# stm32-board-adapter.net
KiCad netlist of a schematic drawn in EAGLE
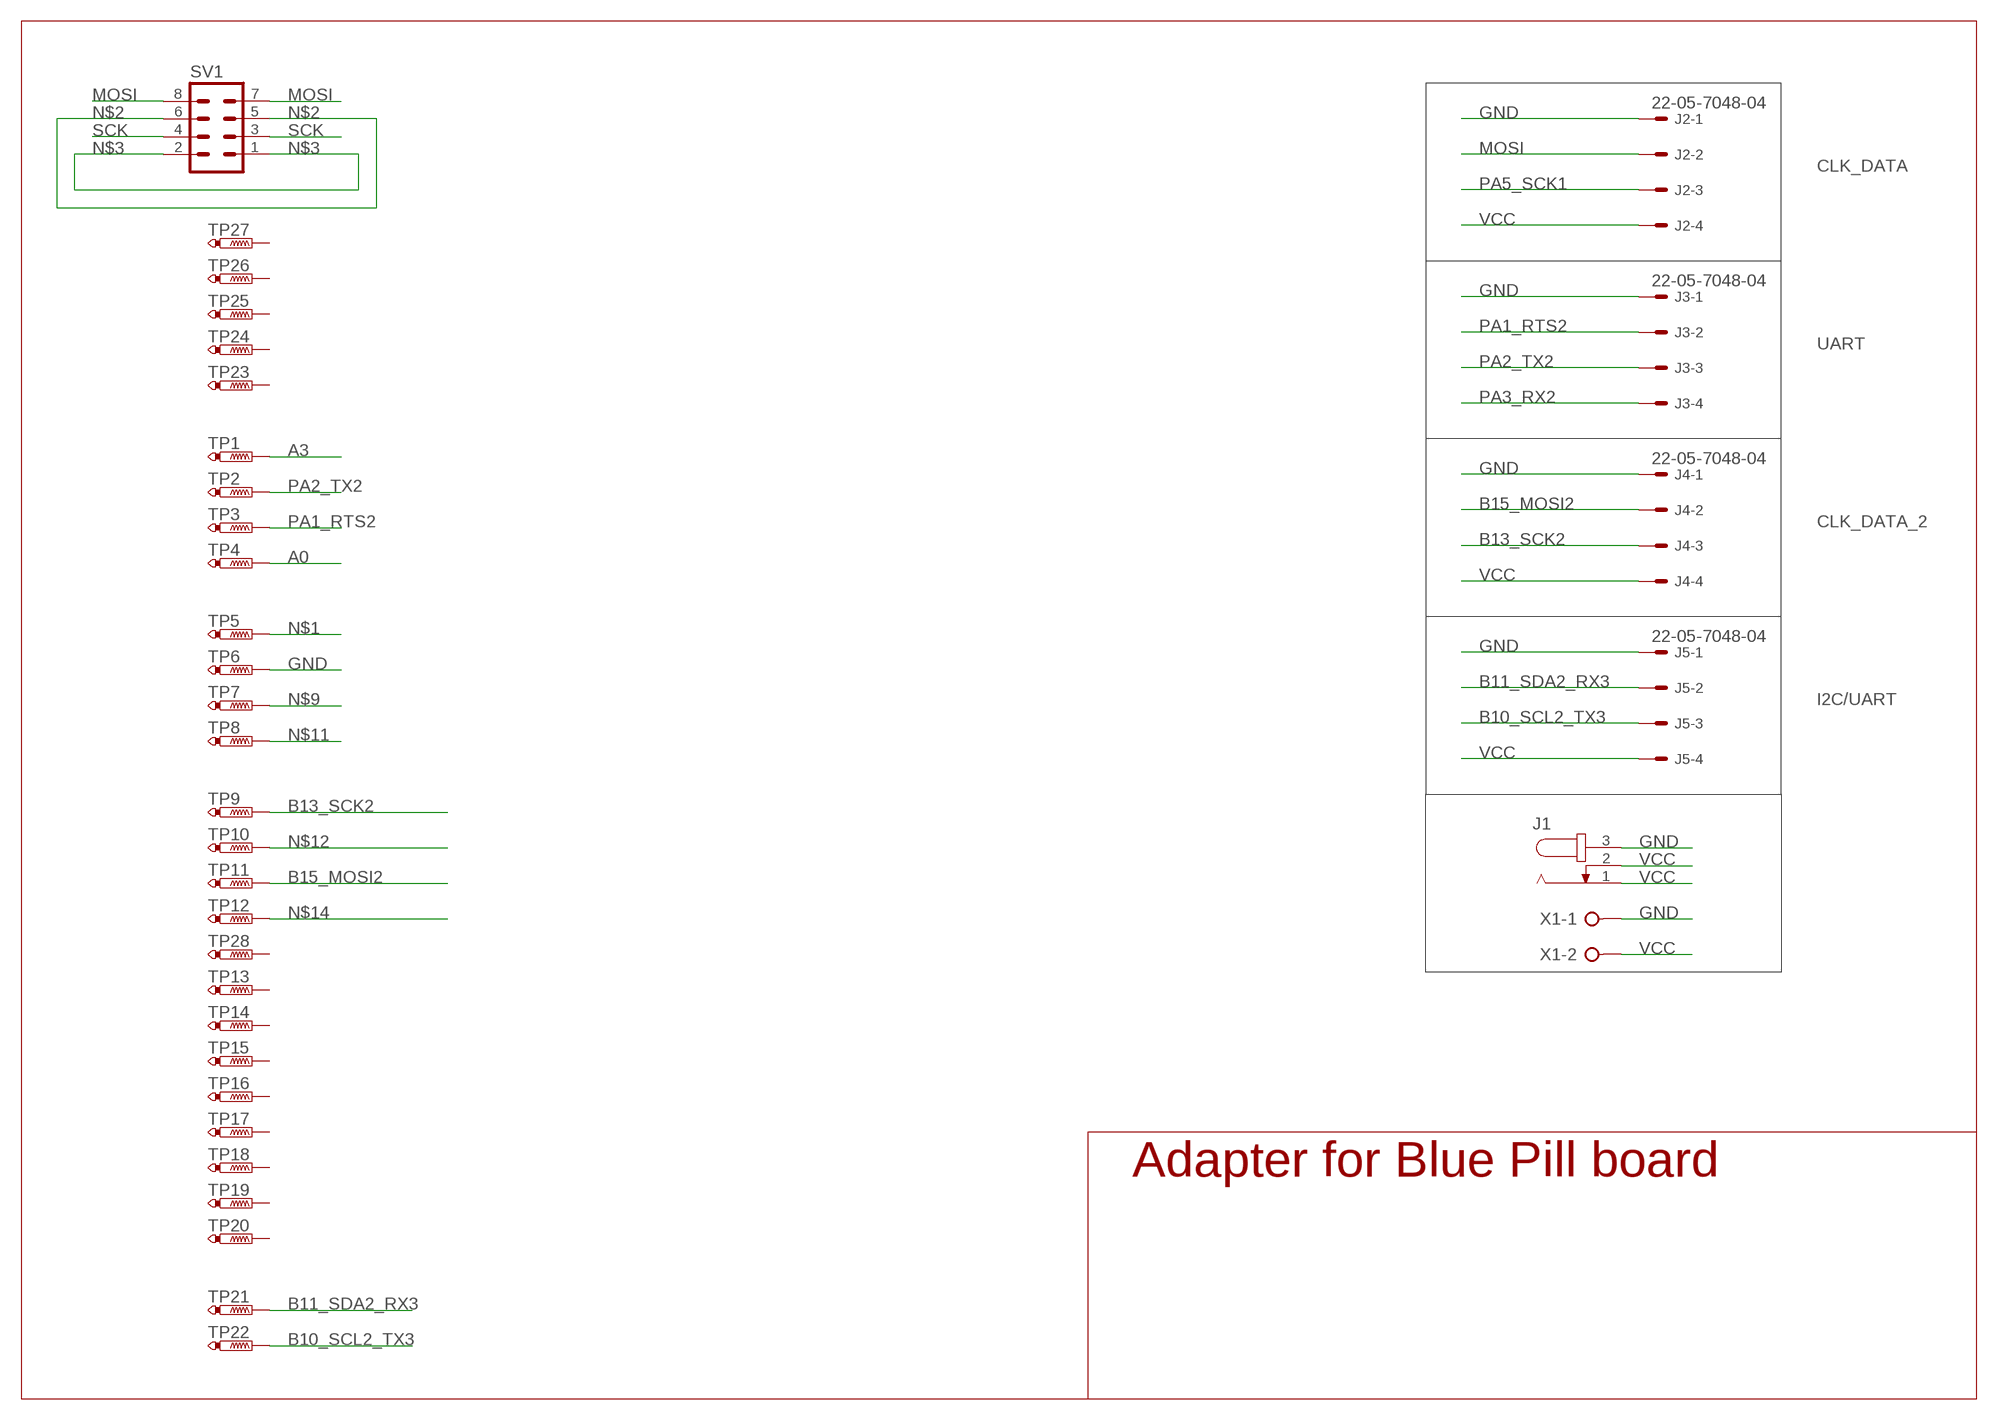
[diagram p0: schematic, sheet 1]

(export (version "E")
  (design (tool "Eeschema 10.0.6"))
  (components
    (comp (ref "J1")
      (value "JACK-PLUG1")
      (footprint "eagle-import:SPC4078")
      (libsource (lib "eagle-import") (part "JACK-PLUG1"))
    )
    (comp (ref "J2")
      (value "22-05-7048-04")
      (footprint "eagle-import:7395-04")
      (libsource (lib "eagle-import") (part "22-?-0405-7048"))
    )
    (comp (ref "J3")
      (value "22-05-7048-04")
      (footprint "eagle-import:7395-04")
      (libsource (lib "eagle-import") (part "22-?-0405-7048"))
    )
    (comp (ref "J4")
      (value "22-05-7048-04")
      (footprint "eagle-import:7395-04")
      (libsource (lib "eagle-import") (part "22-?-0405-7048"))
    )
    (comp (ref "J5")
      (value "22-05-7048-04")
      (footprint "eagle-import:7395-04")
      (libsource (lib "eagle-import") (part "22-?-0405-7048"))
    )
    (comp (ref "SV1")
      (value "MA04-2")
      (footprint "eagle-import:MA04-2")
      (libsource (lib "eagle-import") (part "MA04-2"))
    )
    (comp (ref "TP1")
      (value "PTR1PAD1-13")
      (footprint "eagle-import:P1-13")
      (libsource (lib "eagle-import") (part "PTR1PAD1-13"))
    )
    (comp (ref "TP2")
      (value "PTR1PAD1-13")
      (footprint "eagle-import:P1-13")
      (libsource (lib "eagle-import") (part "PTR1PAD1-13"))
    )
    (comp (ref "TP3")
      (value "PTR1PAD1-13")
      (footprint "eagle-import:P1-13")
      (libsource (lib "eagle-import") (part "PTR1PAD1-13"))
    )
    (comp (ref "TP4")
      (value "PTR1PAD1-13")
      (footprint "eagle-import:P1-13")
      (libsource (lib "eagle-import") (part "PTR1PAD1-13"))
    )
    (comp (ref "TP5")
      (value "PTR1PAD1-13")
      (footprint "eagle-import:P1-13")
      (libsource (lib "eagle-import") (part "PTR1PAD1-13"))
    )
    (comp (ref "TP6")
      (value "PTR1PAD1-13")
      (footprint "eagle-import:P1-13")
      (libsource (lib "eagle-import") (part "PTR1PAD1-13"))
    )
    (comp (ref "TP7")
      (value "PTR1PAD1-13")
      (footprint "eagle-import:P1-13")
      (libsource (lib "eagle-import") (part "PTR1PAD1-13"))
    )
    (comp (ref "TP8")
      (value "PTR1PAD1-13")
      (footprint "eagle-import:P1-13")
      (libsource (lib "eagle-import") (part "PTR1PAD1-13"))
    )
    (comp (ref "TP9")
      (value "PTR1PAD1-13")
      (footprint "eagle-import:P1-13")
      (libsource (lib "eagle-import") (part "PTR1PAD1-13"))
    )
    (comp (ref "TP10")
      (value "PTR1PAD1-13")
      (footprint "eagle-import:P1-13")
      (libsource (lib "eagle-import") (part "PTR1PAD1-13"))
    )
    (comp (ref "TP11")
      (value "PTR1PAD1-13")
      (footprint "eagle-import:P1-13")
      (libsource (lib "eagle-import") (part "PTR1PAD1-13"))
    )
    (comp (ref "TP12")
      (value "PTR1PAD1-13")
      (footprint "eagle-import:P1-13")
      (libsource (lib "eagle-import") (part "PTR1PAD1-13"))
    )
    (comp (ref "TP13")
      (value "PTR1PAD1-13")
      (footprint "eagle-import:P1-13")
      (libsource (lib "eagle-import") (part "PTR1PAD1-13"))
    )
    (comp (ref "TP14")
      (value "PTR1PAD1-13")
      (footprint "eagle-import:P1-13")
      (libsource (lib "eagle-import") (part "PTR1PAD1-13"))
    )
    (comp (ref "TP15")
      (value "PTR1PAD1-13")
      (footprint "eagle-import:P1-13")
      (libsource (lib "eagle-import") (part "PTR1PAD1-13"))
    )
    (comp (ref "TP16")
      (value "PTR1PAD1-13")
      (footprint "eagle-import:P1-13")
      (libsource (lib "eagle-import") (part "PTR1PAD1-13"))
    )
    (comp (ref "TP17")
      (value "PTR1PAD1-13")
      (footprint "eagle-import:P1-13")
      (libsource (lib "eagle-import") (part "PTR1PAD1-13"))
    )
    (comp (ref "TP18")
      (value "PTR1PAD1-13")
      (footprint "eagle-import:P1-13")
      (libsource (lib "eagle-import") (part "PTR1PAD1-13"))
    )
    (comp (ref "TP19")
      (value "PTR1PAD1-13")
      (footprint "eagle-import:P1-13")
      (libsource (lib "eagle-import") (part "PTR1PAD1-13"))
    )
    (comp (ref "TP20")
      (value "PTR1PAD1-13")
      (footprint "eagle-import:P1-13")
      (libsource (lib "eagle-import") (part "PTR1PAD1-13"))
    )
    (comp (ref "TP21")
      (value "PTR1PAD1-13")
      (footprint "eagle-import:P1-13")
      (libsource (lib "eagle-import") (part "PTR1PAD1-13"))
    )
    (comp (ref "TP22")
      (value "PTR1PAD1-13")
      (footprint "eagle-import:P1-13")
      (libsource (lib "eagle-import") (part "PTR1PAD1-13"))
    )
    (comp (ref "TP23")
      (value "PTR1PAD1-13")
      (footprint "eagle-import:P1-13")
      (libsource (lib "eagle-import") (part "PTR1PAD1-13"))
    )
    (comp (ref "TP24")
      (value "PTR1PAD1-13")
      (footprint "eagle-import:P1-13")
      (libsource (lib "eagle-import") (part "PTR1PAD1-13"))
    )
    (comp (ref "TP25")
      (value "PTR1PAD1-13")
      (footprint "eagle-import:P1-13")
      (libsource (lib "eagle-import") (part "PTR1PAD1-13"))
    )
    (comp (ref "TP26")
      (value "PTR1PAD1-13")
      (footprint "eagle-import:P1-13")
      (libsource (lib "eagle-import") (part "PTR1PAD1-13"))
    )
    (comp (ref "TP27")
      (value "PTR1PAD1-13")
      (footprint "eagle-import:P1-13")
      (libsource (lib "eagle-import") (part "PTR1PAD1-13"))
    )
    (comp (ref "TP28")
      (value "PTR1PAD1-13")
      (footprint "eagle-import:P1-13")
      (libsource (lib "eagle-import") (part "PTR1PAD1-13"))
    )
    (comp (ref "X1")
      (value "W237-02P")
      (footprint "eagle-import:W237-132")
      (libsource (lib "eagle-import") (part "W237-02P"))
    )
  )
  (nets
    (net (code "1") (name "/A0") (class "Default")
      (node (ref "TP4") (pin "TP") (pinfunction "TP_TP") (pintype "input"))
    )
    (net (code "2") (name "/A3") (class "Default")
      (node (ref "TP1") (pin "TP") (pinfunction "TP_TP") (pintype "input"))
    )
    (net (code "3") (name "/B10_SCL2_TX3") (class "Default")
      (node (ref "J5") (pin "3") (pinfunction "S_3") (pintype "passive"))
      (node (ref "TP22") (pin "TP") (pinfunction "TP_TP") (pintype "input"))
    )
    (net (code "4") (name "/B11_SDA2_RX3") (class "Default")
      (node (ref "J5") (pin "2") (pinfunction "S_2") (pintype "passive"))
      (node (ref "TP21") (pin "TP") (pinfunction "TP_TP") (pintype "input"))
    )
    (net (code "5") (name "/B13_SCK2") (class "Default")
      (node (ref "J4") (pin "3") (pinfunction "S_3") (pintype "passive"))
      (node (ref "TP9") (pin "TP") (pinfunction "TP_TP") (pintype "input"))
    )
    (net (code "6") (name "/B15_MOSI2") (class "Default")
      (node (ref "J4") (pin "2") (pinfunction "S_2") (pintype "passive"))
      (node (ref "TP11") (pin "TP") (pinfunction "TP_TP") (pintype "input"))
    )
    (net (code "7") (name "/GND") (class "Default")
      (node (ref "J1") (pin "3") (pinfunction "3_3") (pintype "passive"))
      (node (ref "J2") (pin "1") (pinfunction "S_1") (pintype "passive"))
      (node (ref "J3") (pin "1") (pinfunction "S_1") (pintype "passive"))
      (node (ref "J4") (pin "1") (pinfunction "S_1") (pintype "passive"))
      (node (ref "J5") (pin "1") (pinfunction "S_1") (pintype "passive"))
      (node (ref "TP6") (pin "TP") (pinfunction "TP_TP") (pintype "input"))
      (node (ref "X1") (pin "1") (pinfunction "KL_1") (pintype "passive"))
    )
    (net (code "8") (name "/MOSI") (class "Default")
      (node (ref "J2") (pin "2") (pinfunction "S_2") (pintype "passive"))
      (node (ref "SV1") (pin "7") (pinfunction "7_7") (pintype "passive"))
      (node (ref "SV1") (pin "8") (pinfunction "8_8") (pintype "passive"))
    )
    (net (code "9") (name "/N$1") (class "Default")
      (node (ref "TP5") (pin "TP") (pinfunction "TP_TP") (pintype "input"))
    )
    (net (code "10") (name "/N$2") (class "Default")
      (node (ref "SV1") (pin "5") (pinfunction "5_5") (pintype "passive"))
      (node (ref "SV1") (pin "6") (pinfunction "6_6") (pintype "passive"))
    )
    (net (code "11") (name "/N$3") (class "Default")
      (node (ref "SV1") (pin "1") (pinfunction "1_1") (pintype "passive"))
      (node (ref "SV1") (pin "2") (pinfunction "2_2") (pintype "passive"))
    )
    (net (code "12") (name "/N$9") (class "Default")
      (node (ref "TP7") (pin "TP") (pinfunction "TP_TP") (pintype "input"))
    )
    (net (code "13") (name "/N$11") (class "Default")
      (node (ref "TP8") (pin "TP") (pinfunction "TP_TP") (pintype "input"))
    )
    (net (code "14") (name "/N$12") (class "Default")
      (node (ref "TP10") (pin "TP") (pinfunction "TP_TP") (pintype "input"))
    )
    (net (code "15") (name "/N$14") (class "Default")
      (node (ref "TP12") (pin "TP") (pinfunction "TP_TP") (pintype "input"))
    )
    (net (code "16") (name "/PA1_RTS2") (class "Default")
      (node (ref "J3") (pin "2") (pinfunction "S_2") (pintype "passive"))
      (node (ref "TP3") (pin "TP") (pinfunction "TP_TP") (pintype "input"))
    )
    (net (code "17") (name "/PA2_TX2") (class "Default")
      (node (ref "J3") (pin "3") (pinfunction "S_3") (pintype "passive"))
      (node (ref "TP2") (pin "TP") (pinfunction "TP_TP") (pintype "input"))
    )
    (net (code "18") (name "/PA3_RX2") (class "Default")
      (node (ref "J3") (pin "4") (pinfunction "S_4") (pintype "passive"))
    )
    (net (code "19") (name "/PA5_SCK1") (class "Default")
      (node (ref "J2") (pin "3") (pinfunction "S_3") (pintype "passive"))
    )
    (net (code "20") (name "/SCK") (class "Default")
      (node (ref "SV1") (pin "3") (pinfunction "3_3") (pintype "passive"))
      (node (ref "SV1") (pin "4") (pinfunction "4_4") (pintype "passive"))
    )
    (net (code "21") (name "/VCC") (class "Default")
      (node (ref "J1") (pin "1") (pinfunction "1_1") (pintype "passive"))
      (node (ref "J1") (pin "2") (pinfunction "2_2") (pintype "passive"))
      (node (ref "J2") (pin "4") (pinfunction "S_4") (pintype "passive"))
      (node (ref "J4") (pin "4") (pinfunction "S_4") (pintype "passive"))
      (node (ref "J5") (pin "4") (pinfunction "S_4") (pintype "passive"))
      (node (ref "X1") (pin "2") (pinfunction "KL_2") (pintype "passive"))
    )
    (net (code "22") (name "unconnected-(TP13-PadTP)") (class "Default")
      (node (ref "TP13") (pin "TP") (pinfunction "TP_TP") (pintype "input"))
    )
    (net (code "23") (name "unconnected-(TP14-PadTP)") (class "Default")
      (node (ref "TP14") (pin "TP") (pinfunction "TP_TP") (pintype "input"))
    )
    (net (code "24") (name "unconnected-(TP15-PadTP)") (class "Default")
      (node (ref "TP15") (pin "TP") (pinfunction "TP_TP") (pintype "input"))
    )
    (net (code "25") (name "unconnected-(TP16-PadTP)") (class "Default")
      (node (ref "TP16") (pin "TP") (pinfunction "TP_TP") (pintype "input"))
    )
    (net (code "26") (name "unconnected-(TP17-PadTP)") (class "Default")
      (node (ref "TP17") (pin "TP") (pinfunction "TP_TP") (pintype "input"))
    )
    (net (code "27") (name "unconnected-(TP18-PadTP)") (class "Default")
      (node (ref "TP18") (pin "TP") (pinfunction "TP_TP") (pintype "input"))
    )
    (net (code "28") (name "unconnected-(TP19-PadTP)") (class "Default")
      (node (ref "TP19") (pin "TP") (pinfunction "TP_TP") (pintype "input"))
    )
    (net (code "29") (name "unconnected-(TP20-PadTP)") (class "Default")
      (node (ref "TP20") (pin "TP") (pinfunction "TP_TP") (pintype "input"))
    )
    (net (code "30") (name "unconnected-(TP23-PadTP)") (class "Default")
      (node (ref "TP23") (pin "TP") (pinfunction "TP_TP") (pintype "input"))
    )
    (net (code "31") (name "unconnected-(TP24-PadTP)") (class "Default")
      (node (ref "TP24") (pin "TP") (pinfunction "TP_TP") (pintype "input"))
    )
    (net (code "32") (name "unconnected-(TP25-PadTP)") (class "Default")
      (node (ref "TP25") (pin "TP") (pinfunction "TP_TP") (pintype "input"))
    )
    (net (code "33") (name "unconnected-(TP26-PadTP)") (class "Default")
      (node (ref "TP26") (pin "TP") (pinfunction "TP_TP") (pintype "input"))
    )
    (net (code "34") (name "unconnected-(TP27-PadTP)") (class "Default")
      (node (ref "TP27") (pin "TP") (pinfunction "TP_TP") (pintype "input"))
    )
    (net (code "35") (name "unconnected-(TP28-PadTP)") (class "Default")
      (node (ref "TP28") (pin "TP") (pinfunction "TP_TP") (pintype "input"))
    )
  )
)
